# schematic.net
KiCad netlist of a schematic drawn in EasyEDA
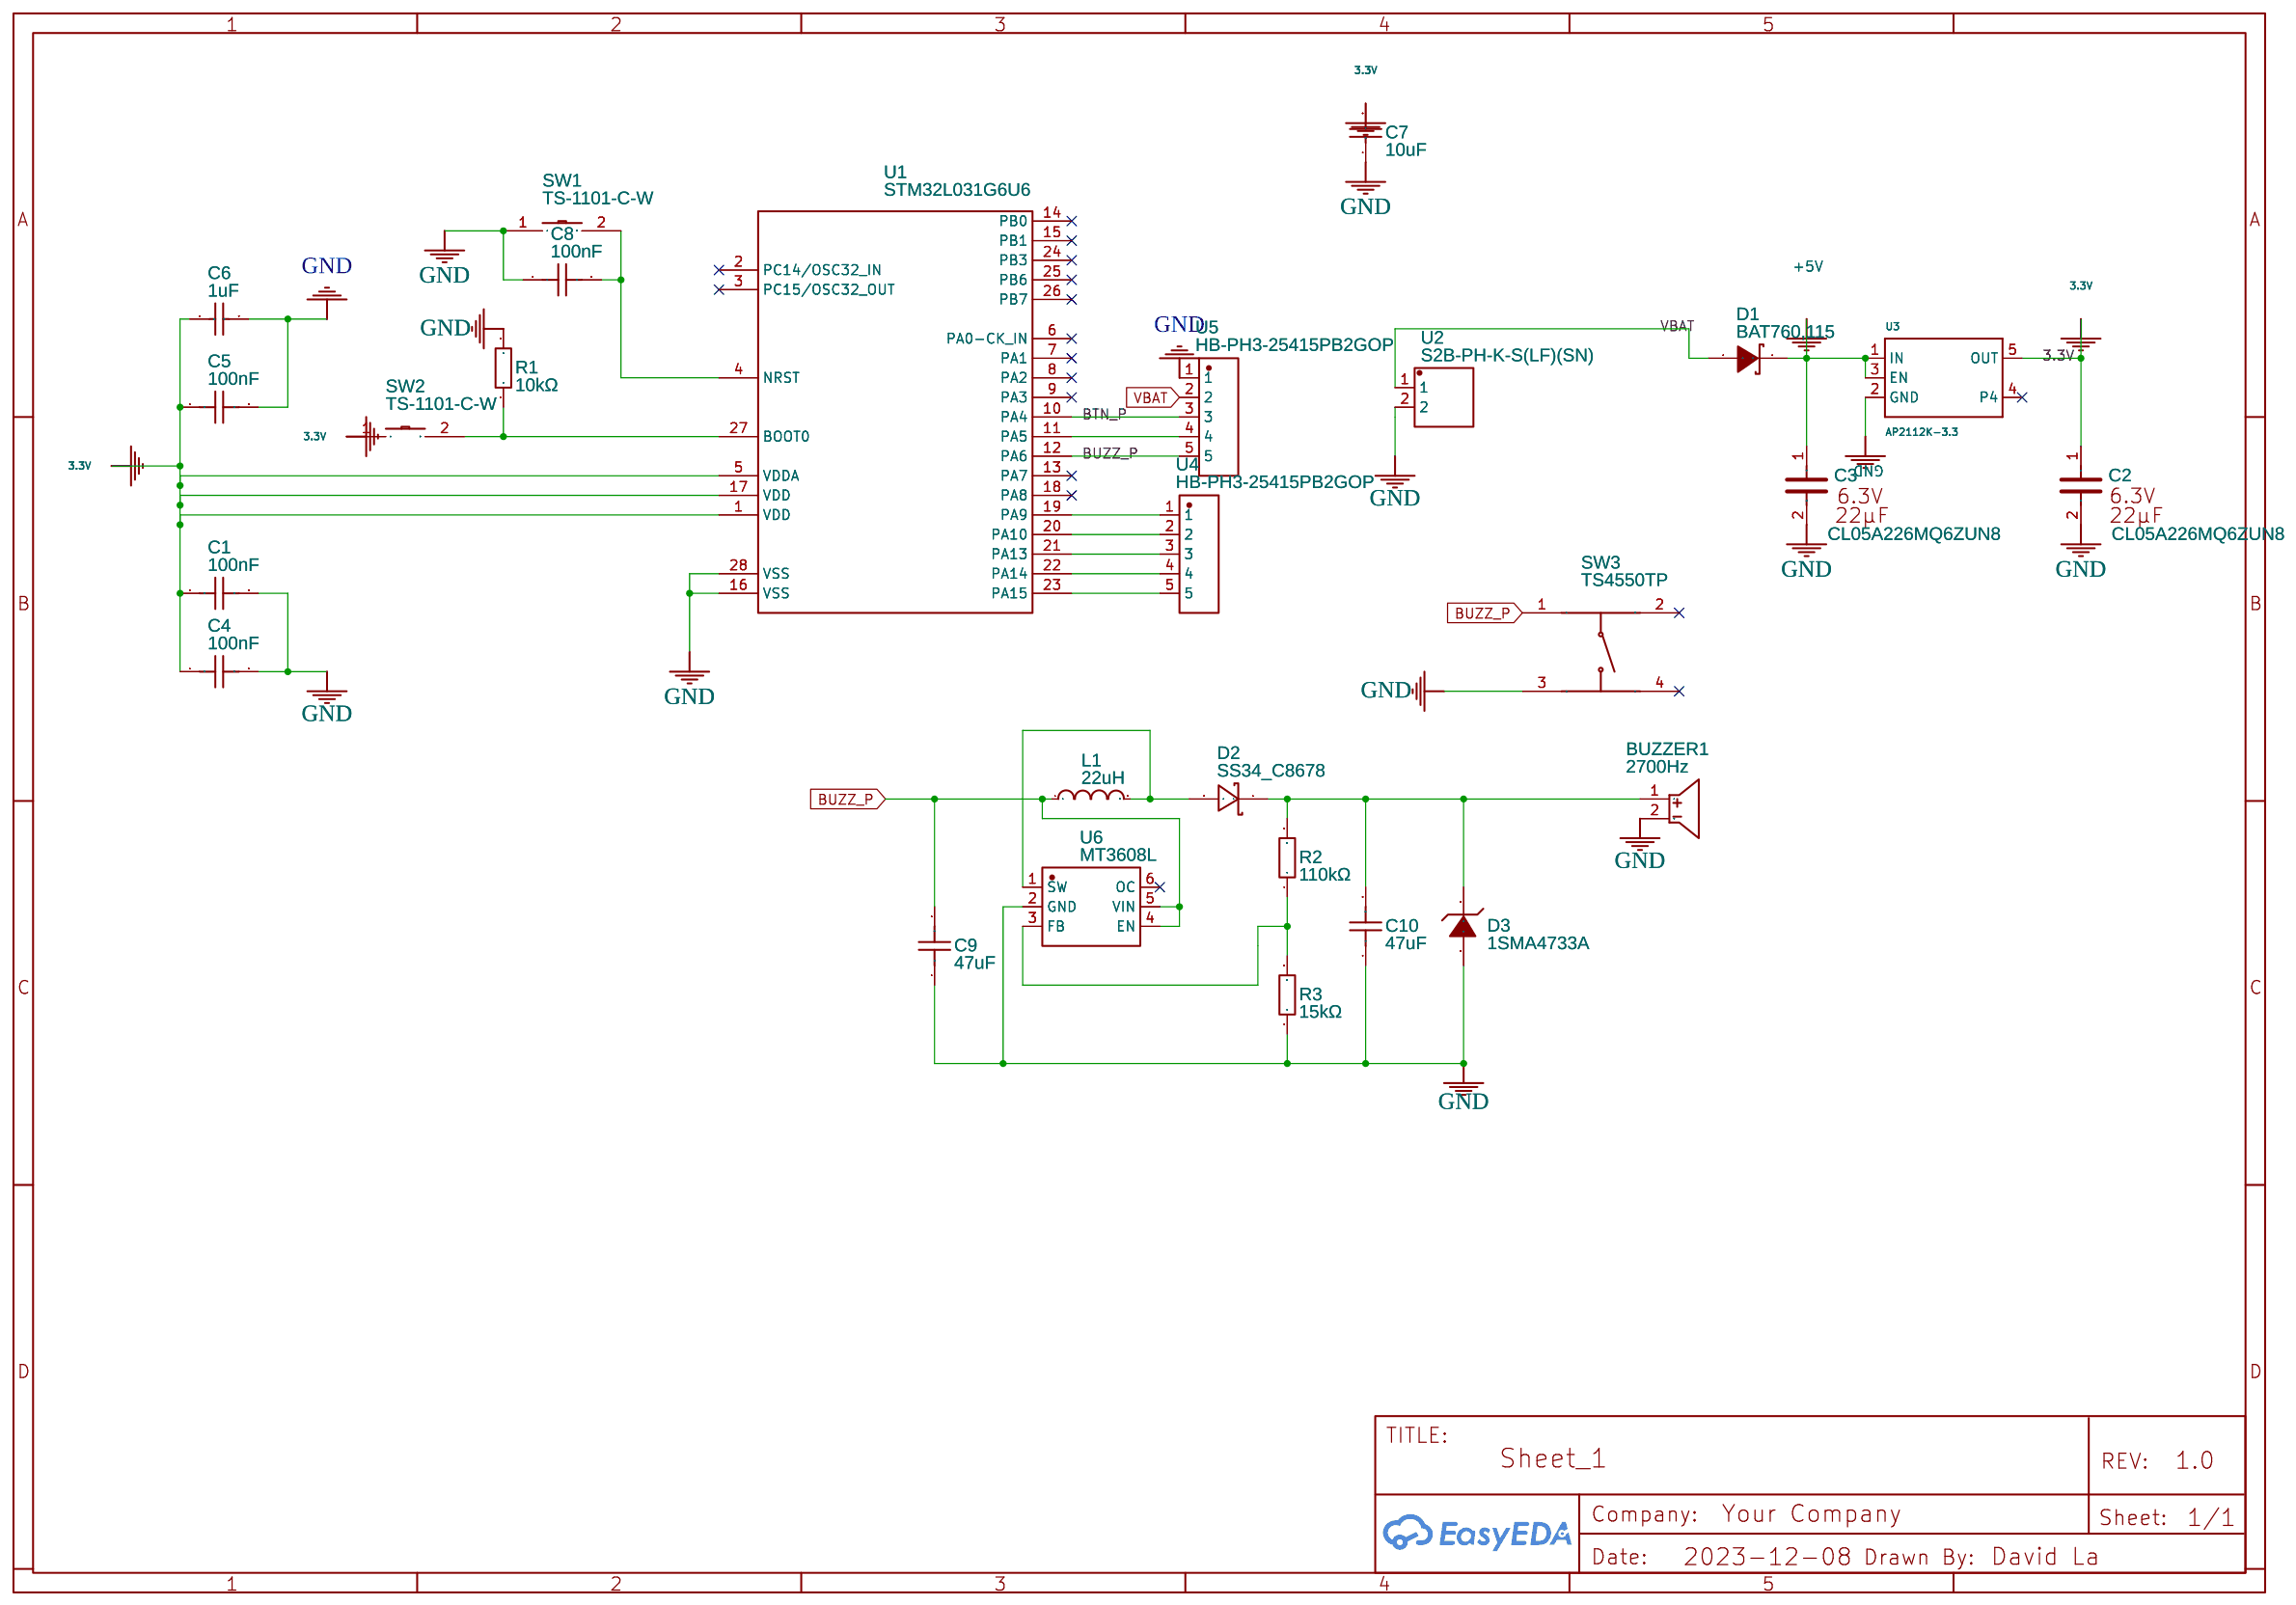
[diagram p0: schematic sheet]

(export (version "E")
  (design (tool "Eeschema 10.0.6"))
  (components
    (comp (ref "BUZZER1")
      (value "2700Hz")
      (fields (field (name "Manufacturer Part") "GPC2316YB-5V") (field (name "Manufacturer") "INGHAi(赢海)"))
      (libsource (lib "") (part "GPC2316YB-5V"))
    )
    (comp (ref "C1")
      (value "100nF")
      (fields
        (field (name "Manufacturer Part") "TCC0402X5R104M250AT")
        (field (name "Manufacturer") "CCTC(三环)")
      )
      (libsource (lib "") (part "TCC0402X5R104M250AT"))
    )
    (comp (ref "C2")
      (value "CL05A226MQ6ZUN8")
      (fields
        (field (name "Manufacturer Part") "GRM155R60J226ME11D")
        (field (name "Manufacturer") "muRata(村田)")
      )
      (libsource (lib "") (part "SAMSUNG_CL05A226MQ6ZUN8SAMSUNG_CL05A226MQ6ZUN8_0_0"))
    )
    (comp (ref "C3")
      (value "CL05A226MQ6ZUN8")
      (fields
        (field (name "Manufacturer Part") "GRM155R60J226ME11D")
        (field (name "Manufacturer") "muRata(村田)")
      )
      (libsource (lib "") (part "SAMSUNG_CL05A226MQ6ZUN8SAMSUNG_CL05A226MQ6ZUN8_0_0_1"))
    )
    (comp (ref "C4")
      (value "100nF")
      (fields
        (field (name "Manufacturer Part") "TCC0402X5R104M250AT")
        (field (name "Manufacturer") "CCTC(三环)")
      )
      (libsource (lib "") (part "TCC0402X5R104M250AT"))
    )
    (comp (ref "C5")
      (value "100nF")
      (fields
        (field (name "Manufacturer Part") "TCC0402X5R104M250AT")
        (field (name "Manufacturer") "CCTC(三环)")
      )
      (libsource (lib "") (part "TCC0402X5R104M250AT"))
    )
    (comp (ref "C6")
      (value "1uF")
      (fields
        (field (name "Manufacturer Part") "CL05A105KP5NNNC")
        (field (name "Manufacturer") "SAMSUNG(三星)")
      )
      (libsource (lib "") (part "CL05A105KP5NNNC"))
    )
    (comp (ref "C7")
      (value "10uF")
      (fields
        (field (name "Manufacturer Part") "CL05A106MQ5NUNC")
        (field (name "Manufacturer") "SAMSUNG(三星)")
      )
      (libsource (lib "") (part "CL05A106MQ5NUNC"))
    )
    (comp (ref "C8")
      (value "100nF")
      (fields
        (field (name "Manufacturer Part") "TCC0402X5R104M250AT")
        (field (name "Manufacturer") "CCTC(三环)")
      )
      (libsource (lib "") (part "TCC0402X5R104M250AT"))
    )
    (comp (ref "C9")
      (value "47uF")
      (fields
        (field (name "Manufacturer Part") "CL21A476MQYNNNE")
        (field (name "Manufacturer") "SAMSUNG(三星)")
      )
      (libsource (lib "") (part "CL10A476MQ8QRNC"))
    )
    (comp (ref "C10")
      (value "47uF")
      (fields
        (field (name "Manufacturer Part") "CL21A476MQYNNNE")
        (field (name "Manufacturer") "SAMSUNG(三星)")
      )
      (libsource (lib "") (part "CL10A476MQ8QRNC"))
    )
    (comp (ref "D1")
      (value "BAT760,115")
      (fields (field (name "Manufacturer") "Nexperia(安世)"))
      (libsource (lib "") (part "BAT760,115"))
    )
    (comp (ref "D2")
      (value "SS34_C8678")
      (fields (field (name "Manufacturer Part") "SS34") (field (name "Manufacturer") "MDD"))
      (libsource (lib "") (part "SS34_C8678"))
    )
    (comp (ref "D3")
      (value "1SMA4733A")
      (fields (field (name "Manufacturer") "MDD"))
      (libsource (lib "") (part "1SMA4733A"))
    )
    (comp (ref "L1")
      (value "22uH")
      (fields (field (name "Manufacturer Part") "SMDRI127-220MT") (field (name "Manufacturer") "SXN(顺翔诺)"))
      (libsource (lib "") (part "SMDRI127-220MT"))
    )
    (comp (ref "R1")
      (value "10kΩ")
      (fields (field (name "Manufacturer Part") "RC0402JR-0710KL") (field (name "Manufacturer") "YAGEO(国巨)"))
      (libsource (lib "") (part "RC0402JR-0710KL"))
    )
    (comp (ref "R2")
      (value "110kΩ")
      (fields (field (name "Manufacturer Part") "RC0402FR-07110KL") (field (name "Manufacturer") "YAGEO(国巨)"))
      (libsource (lib "") (part "RC0402FR-07110KL"))
    )
    (comp (ref "R3")
      (value "15kΩ")
      (fields (field (name "Manufacturer Part") "RC0402FR-0715KL") (field (name "Manufacturer") "YAGEO(国巨)"))
      (libsource (lib "") (part "RC0402FR-0715KL"))
    )
    (comp (ref "SW1")
      (value "TS-1101-C-W")
      (fields (field (name "Manufacturer") "XKB Connectivity(中国星坤)"))
      (libsource (lib "") (part "TS-1101-C-W"))
    )
    (comp (ref "SW2")
      (value "TS-1101-C-W")
      (fields (field (name "Manufacturer") "XKB Connectivity(中国星坤)"))
      (libsource (lib "") (part "TS-1101-C-W"))
    )
    (comp (ref "SW3")
      (value "TS4550TP")
      (fields (field (name "Manufacturer") "SHOU HAN(首韩)"))
      (libsource (lib "") (part "TS4550TP"))
    )
    (comp (ref "U1")
      (value "STM32L031G6U6")
      (fields (field (name "Manufacturer") "ST(意法半导体)"))
      (libsource (lib "") (part "STM32L031G6U6"))
    )
    (comp (ref "U2")
      (value "S2B-PH-K-S(LF)(SN)")
      (fields (field (name "Manufacturer") "JST"))
      (libsource (lib "") (part "S2B-PH-K-S(LF)(SN)"))
    )
    (comp (ref "U3")
      (value "AP2112K-3.3")
      (fields (field (name "Manufacturer Part") "AP2112K-3.3TRG1") (field (name "Manufacturer") "DIODES(美台)"))
      (libsource (lib "") (part "Unknown_985_-620"))
    )
    (comp (ref "U4")
      (value "HB-PH3-25415PB2GOP")
      (fields (field (name "Manufacturer") "HANBO(汉博)"))
      (libsource (lib "") (part "HB-PH3-25415PB2GOP"))
    )
    (comp (ref "U5")
      (value "HB-PH3-25415PB2GOP")
      (fields (field (name "Manufacturer") "HANBO(汉博)"))
      (libsource (lib "") (part "HB-PH3-25415PB2GOP"))
    )
    (comp (ref "U6")
      (value "MT3608L")
      (fields (field (name "Manufacturer") "西安航天民芯"))
      (libsource (lib "") (part "MT3608L"))
    )
  )
  (nets
    (net (code "1") (name "+5V") (class "Default")
      (node (ref "C3") (pin "1") (pinfunction "1_1") (pintype "bidirectional"))
      (node (ref "D1") (pin "1") (pinfunction "K_1") (pintype "unspecified"))
      (node (ref "U3") (pin "1") (pinfunction "IN_1") (pintype "bidirectional"))
      (node (ref "U3") (pin "3") (pinfunction "EN_3") (pintype "bidirectional"))
    )
    (net (code "2") (name "/BTN_P") (class "Default")
      (node (ref "U1") (pin "10") (pinfunction "PA4_10") (pintype "bidirectional"))
      (node (ref "U5") (pin "3") (pinfunction "3_3") (pintype "unspecified"))
    )
    (net (code "3") (name "3.3V") (class "Default")
      (node (ref "C1") (pin "1") (pinfunction "1_1") (pintype "unspecified"))
      (node (ref "C2") (pin "1") (pinfunction "1_1") (pintype "bidirectional"))
      (node (ref "C4") (pin "1") (pinfunction "1_1") (pintype "unspecified"))
      (node (ref "C5") (pin "1") (pinfunction "1_1") (pintype "unspecified"))
      (node (ref "C6") (pin "1") (pinfunction "1_1") (pintype "input"))
      (node (ref "C7") (pin "2") (pinfunction "2_2") (pintype "input"))
      (node (ref "SW2") (pin "1") (pinfunction "1_1") (pintype "unspecified"))
      (node (ref "U1") (pin "1") (pinfunction "VDD_1") (pintype "input"))
      (node (ref "U1") (pin "17") (pinfunction "VDD_17") (pintype "bidirectional"))
      (node (ref "U1") (pin "5") (pinfunction "VDDA_5") (pintype "bidirectional"))
      (node (ref "U3") (pin "5") (pinfunction "OUT_5") (pintype "bidirectional"))
    )
    (net (code "4") (name "BUZZ_P") (class "Default")
      (node (ref "C9") (pin "2") (pinfunction "2_2") (pintype "unspecified"))
      (node (ref "L1") (pin "1") (pinfunction "1_1") (pintype "unspecified"))
      (node (ref "SW3") (pin "1") (pinfunction "1_1") (pintype "unspecified"))
      (node (ref "U1") (pin "12") (pinfunction "PA6_12") (pintype "bidirectional"))
      (node (ref "U5") (pin "5") (pinfunction "5_5") (pintype "unspecified"))
      (node (ref "U6") (pin "4") (pinfunction "EN_4") (pintype "unspecified"))
      (node (ref "U6") (pin "5") (pinfunction "VIN_5") (pintype "unspecified"))
    )
    (net (code "5") (name "GND") (class "Default")
      (node (ref "BUZZER1") (pin "2") (pinfunction "2_2") (pintype "unspecified"))
      (node (ref "C1") (pin "2") (pinfunction "2_2") (pintype "unspecified"))
      (node (ref "C10") (pin "1") (pinfunction "1_1") (pintype "unspecified"))
      (node (ref "C2") (pin "2") (pinfunction "2_2") (pintype "bidirectional"))
      (node (ref "C3") (pin "2") (pinfunction "2_2") (pintype "bidirectional"))
      (node (ref "C4") (pin "2") (pinfunction "2_2") (pintype "unspecified"))
      (node (ref "C5") (pin "2") (pinfunction "2_2") (pintype "unspecified"))
      (node (ref "C6") (pin "2") (pinfunction "2_2") (pintype "input"))
      (node (ref "C7") (pin "1") (pinfunction "1_1") (pintype "input"))
      (node (ref "C8") (pin "1") (pinfunction "1_1") (pintype "unspecified"))
      (node (ref "C9") (pin "1") (pinfunction "1_1") (pintype "unspecified"))
      (node (ref "D3") (pin "2") (pinfunction "A_2") (pintype "unspecified"))
      (node (ref "R1") (pin "2") (pinfunction "2_2") (pintype "input"))
      (node (ref "R3") (pin "1") (pinfunction "1_1") (pintype "input"))
      (node (ref "SW1") (pin "1") (pinfunction "1_1") (pintype "unspecified"))
      (node (ref "SW3") (pin "3") (pinfunction "3_3") (pintype "unspecified"))
      (node (ref "U1") (pin "16") (pinfunction "VSS_16") (pintype "bidirectional"))
      (node (ref "U1") (pin "28") (pinfunction "VSS_28") (pintype "bidirectional"))
      (node (ref "U2") (pin "2") (pinfunction "2_2") (pintype "unspecified"))
      (node (ref "U3") (pin "2") (pinfunction "GND_2") (pintype "bidirectional"))
      (node (ref "U5") (pin "1") (pinfunction "1_1") (pintype "unspecified"))
      (node (ref "U6") (pin "2") (pinfunction "GND_2") (pintype "unspecified"))
    )
    (net (code "6") (name "Net-(D2-A)") (class "Default")
      (node (ref "D2") (pin "2") (pinfunction "A_2") (pintype "unspecified"))
      (node (ref "L1") (pin "2") (pinfunction "2_2") (pintype "unspecified"))
      (node (ref "U6") (pin "1") (pinfunction "SW_1") (pintype "unspecified"))
    )
    (net (code "7") (name "Net-(D2-K)") (class "Default")
      (node (ref "BUZZER1") (pin "1") (pinfunction "1_1") (pintype "unspecified"))
      (node (ref "C10") (pin "2") (pinfunction "2_2") (pintype "unspecified"))
      (node (ref "D2") (pin "1") (pinfunction "K_1") (pintype "unspecified"))
      (node (ref "D3") (pin "1") (pinfunction "K_1") (pintype "unspecified"))
      (node (ref "R2") (pin "2") (pinfunction "2_2") (pintype "input"))
    )
    (net (code "8") (name "Net-(U1-BOOT0)") (class "Default")
      (node (ref "R1") (pin "1") (pinfunction "1_1") (pintype "input"))
      (node (ref "SW2") (pin "2") (pinfunction "2_2") (pintype "unspecified"))
      (node (ref "U1") (pin "27") (pinfunction "BOOT0_27") (pintype "bidirectional"))
    )
    (net (code "9") (name "Net-(U1-NRST)") (class "Default")
      (node (ref "C8") (pin "2") (pinfunction "2_2") (pintype "unspecified"))
      (node (ref "SW1") (pin "2") (pinfunction "2_2") (pintype "unspecified"))
      (node (ref "U1") (pin "4") (pinfunction "NRST_4") (pintype "input"))
    )
    (net (code "10") (name "Net-(U1-PA5)") (class "Default")
      (node (ref "U1") (pin "11") (pinfunction "PA5_11") (pintype "bidirectional"))
      (node (ref "U5") (pin "4") (pinfunction "4_4") (pintype "unspecified"))
    )
    (net (code "11") (name "Net-(U1-PA9)") (class "Default")
      (node (ref "U1") (pin "19") (pinfunction "PA9_19") (pintype "bidirectional"))
      (node (ref "U4") (pin "1") (pinfunction "1_1") (pintype "unspecified"))
    )
    (net (code "12") (name "Net-(U1-PA10)") (class "Default")
      (node (ref "U1") (pin "20") (pinfunction "PA10_20") (pintype "bidirectional"))
      (node (ref "U4") (pin "2") (pinfunction "2_2") (pintype "unspecified"))
    )
    (net (code "13") (name "Net-(U1-PA13)") (class "Default")
      (node (ref "U1") (pin "21") (pinfunction "PA13_21") (pintype "bidirectional"))
      (node (ref "U4") (pin "3") (pinfunction "3_3") (pintype "unspecified"))
    )
    (net (code "14") (name "Net-(U1-PA14)") (class "Default")
      (node (ref "U1") (pin "22") (pinfunction "PA14_22") (pintype "bidirectional"))
      (node (ref "U4") (pin "4") (pinfunction "4_4") (pintype "unspecified"))
    )
    (net (code "15") (name "Net-(U1-PA15)") (class "Default")
      (node (ref "U1") (pin "23") (pinfunction "PA15_23") (pintype "bidirectional"))
      (node (ref "U4") (pin "5") (pinfunction "5_5") (pintype "unspecified"))
    )
    (net (code "16") (name "Net-(U6-FB)") (class "Default")
      (node (ref "R2") (pin "1") (pinfunction "1_1") (pintype "input"))
      (node (ref "R3") (pin "2") (pinfunction "2_2") (pintype "input"))
      (node (ref "U6") (pin "3") (pinfunction "FB_3") (pintype "unspecified"))
    )
    (net (code "17") (name "VBAT") (class "Default")
      (node (ref "D1") (pin "2") (pinfunction "A_2") (pintype "unspecified"))
      (node (ref "U2") (pin "1") (pinfunction "1_1") (pintype "unspecified"))
      (node (ref "U5") (pin "2") (pinfunction "2_2") (pintype "unspecified"))
    )
    (net (code "18") (name "unconnected-(SW3-Pad2)") (class "Default")
      (node (ref "SW3") (pin "2") (pinfunction "2_2") (pintype "unspecified+no_connect"))
    )
    (net (code "19") (name "unconnected-(SW3-Pad4)") (class "Default")
      (node (ref "SW3") (pin "4") (pinfunction "4_4") (pintype "unspecified+no_connect"))
    )
    (net (code "20") (name "unconnected-(U1-PA0-CK_IN-Pad6)") (class "Default")
      (node (ref "U1") (pin "6") (pinfunction "PA0-CK_IN_6") (pintype "bidirectional+no_connect"))
    )
    (net (code "21") (name "unconnected-(U1-PA1-Pad7)") (class "Default")
      (node (ref "U1") (pin "7") (pinfunction "PA1_7") (pintype "bidirectional+no_connect"))
    )
    (net (code "22") (name "unconnected-(U1-PA2-Pad8)") (class "Default")
      (node (ref "U1") (pin "8") (pinfunction "PA2_8") (pintype "bidirectional+no_connect"))
    )
    (net (code "23") (name "unconnected-(U1-PA3-Pad9)") (class "Default")
      (node (ref "U1") (pin "9") (pinfunction "PA3_9") (pintype "bidirectional+no_connect"))
    )
    (net (code "24") (name "unconnected-(U1-PA7-Pad13)") (class "Default")
      (node (ref "U1") (pin "13") (pinfunction "PA7_13") (pintype "bidirectional+no_connect"))
    )
    (net (code "25") (name "unconnected-(U1-PA8-Pad18)") (class "Default")
      (node (ref "U1") (pin "18") (pinfunction "PA8_18") (pintype "bidirectional+no_connect"))
    )
    (net (code "26") (name "unconnected-(U1-PB0-Pad14)") (class "Default")
      (node (ref "U1") (pin "14") (pinfunction "PB0_14") (pintype "bidirectional+no_connect"))
    )
    (net (code "27") (name "unconnected-(U1-PB1-Pad15)") (class "Default")
      (node (ref "U1") (pin "15") (pinfunction "PB1_15") (pintype "bidirectional+no_connect"))
    )
    (net (code "28") (name "unconnected-(U1-PB3-Pad24)") (class "Default")
      (node (ref "U1") (pin "24") (pinfunction "PB3_24") (pintype "bidirectional+no_connect"))
    )
    (net (code "29") (name "unconnected-(U1-PB6-Pad25)") (class "Default")
      (node (ref "U1") (pin "25") (pinfunction "PB6_25") (pintype "bidirectional+no_connect"))
    )
    (net (code "30") (name "unconnected-(U1-PB7-Pad26)") (class "Default")
      (node (ref "U1") (pin "26") (pinfunction "PB7_26") (pintype "bidirectional+no_connect"))
    )
    (net (code "31") (name "unconnected-(U1-PC14{slash}OSC32_IN-Pad2)") (class "Default")
      (node (ref "U1") (pin "2") (pinfunction "PC14/OSC32_IN_2") (pintype "bidirectional+no_connect"))
    )
    (net (code "32") (name "unconnected-(U1-PC15{slash}OSC32_OUT-Pad3)") (class "Default")
      (node (ref "U1") (pin "3") (pinfunction "PC15/OSC32_OUT_3") (pintype "bidirectional+no_connect"))
    )
    (net (code "33") (name "unconnected-(U3-P4-Pad4)") (class "Default")
      (node (ref "U3") (pin "4") (pinfunction "P4_4") (pintype "bidirectional+no_connect"))
    )
    (net (code "34") (name "unconnected-(U6-OC-Pad6)") (class "Default")
      (node (ref "U6") (pin "6") (pinfunction "OC_6") (pintype "unspecified+no_connect"))
    )
  )
)
